# STM32F030.net
KiCad netlist of a schematic drawn in Altium Designer
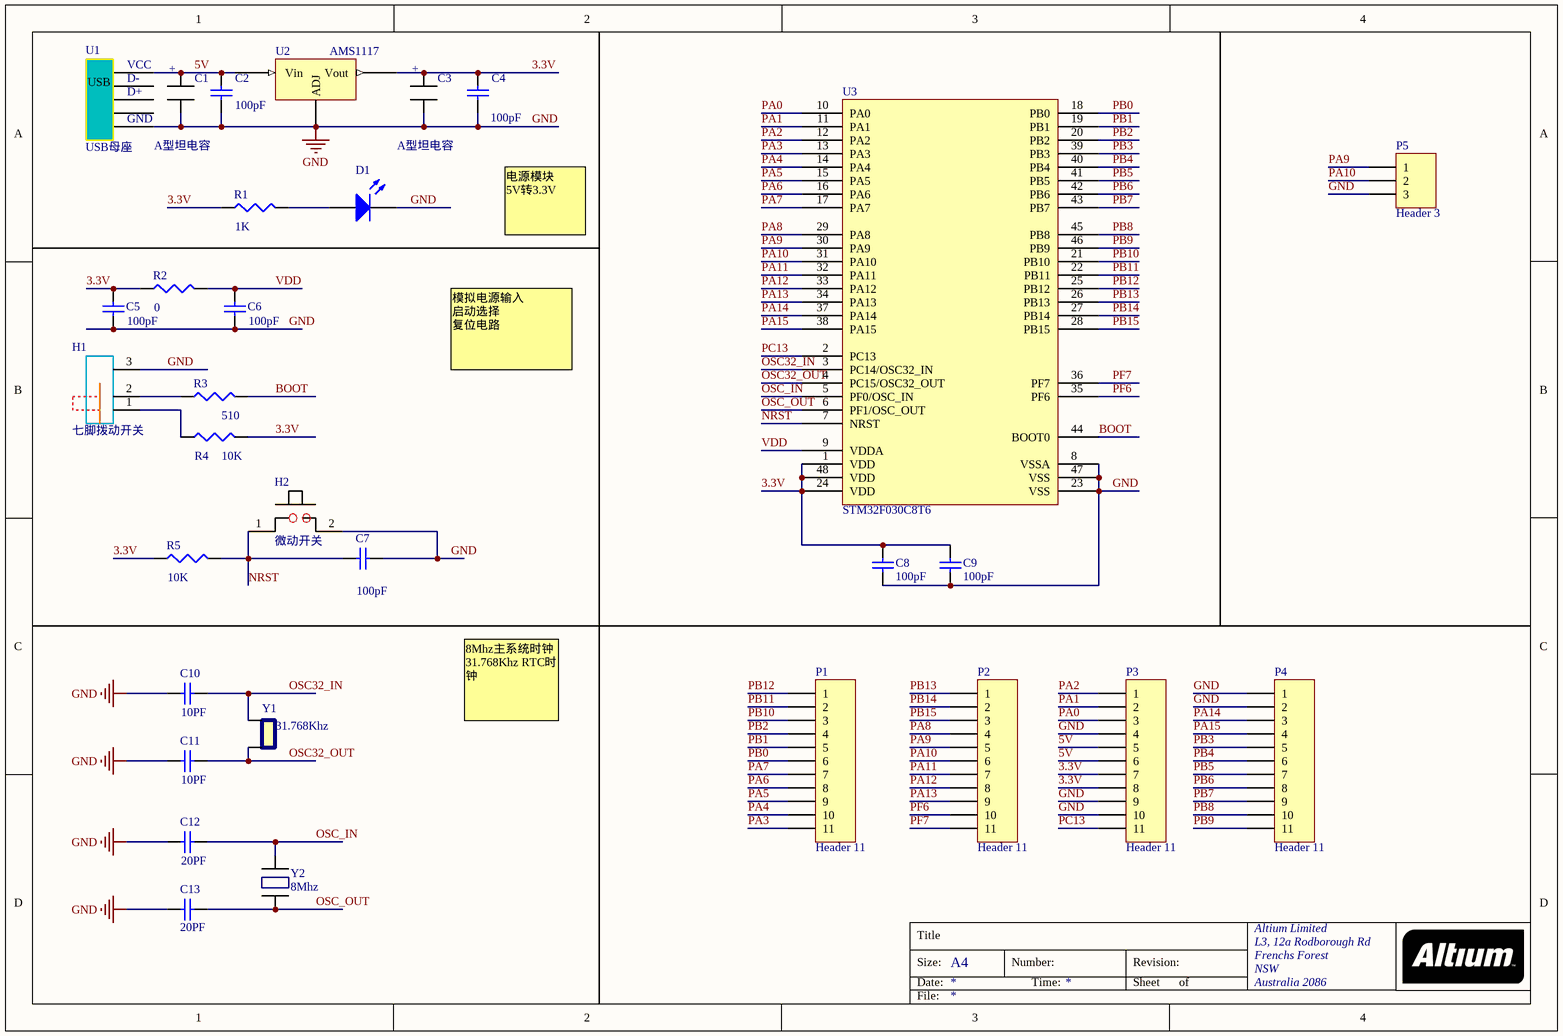
[diagram p0: STM32F030.SchDoc]

(export (version "E")
  (design (tool "Eeschema 10.0.6"))
  (components
    (comp (ref "C1")
      (value "A型坦电容")
      (footprint "A型坦电容")
      (description "C?")
      (libsource (lib "AD元件库") (part "A型坦电容"))
    )
    (comp (ref "C2")
      (value "100pF")
      (footprint "C1206")
      (description "Capacitor (Semiconductor SIM Model)")
      (fields (field (name "Comment") "0.1UF") (field (name "PUBLISHER") "Altium Limited"))
      (libsource (lib "Miscellaneous Devices") (part "Cap Semi"))
    )
    (comp (ref "C3")
      (value "A型坦电容")
      (footprint "A型坦电容")
      (description "C?")
      (libsource (lib "AD元件库") (part "A型坦电容"))
    )
    (comp (ref "C4")
      (value "100pF")
      (footprint "C1206")
      (description "Capacitor (Semiconductor SIM Model)")
      (fields (field (name "Comment") "0.1UF") (field (name "PUBLISHER") "Altium Limited"))
      (libsource (lib "Miscellaneous Devices") (part "Cap Semi"))
    )
    (comp (ref "C5")
      (value "100pF")
      (footprint "C1206")
      (description "Capacitor (Semiconductor SIM Model)")
      (fields (field (name "Comment") "0.1UF") (field (name "PUBLISHER") "Altium Limited"))
      (libsource (lib "Miscellaneous Devices") (part "Cap Semi"))
    )
    (comp (ref "C6")
      (value "100pF")
      (footprint "C1206")
      (description "Capacitor (Semiconductor SIM Model)")
      (fields (field (name "Comment") "0.1UF") (field (name "PUBLISHER") "Altium Limited"))
      (libsource (lib "Miscellaneous Devices") (part "Cap Semi"))
    )
    (comp (ref "C7")
      (value "100pF")
      (footprint "C1206")
      (description "Capacitor (Semiconductor SIM Model)")
      (fields (field (name "Comment") "0.1UF") (field (name "PUBLISHER") "Altium Limited"))
      (libsource (lib "Miscellaneous Devices") (part "Cap Semi"))
    )
    (comp (ref "C8")
      (value "100pF")
      (footprint "C1206")
      (description "Capacitor (Semiconductor SIM Model)")
      (fields (field (name "Comment") "0.1UF") (field (name "PUBLISHER") "Altium Limited"))
      (libsource (lib "Miscellaneous Devices") (part "Cap Semi"))
    )
    (comp (ref "C9")
      (value "100pF")
      (footprint "C1206")
      (description "Capacitor (Semiconductor SIM Model)")
      (fields (field (name "Comment") "0.1UF") (field (name "PUBLISHER") "Altium Limited"))
      (libsource (lib "Miscellaneous Devices") (part "Cap Semi"))
    )
    (comp (ref "C10")
      (value "10PF")
      (footprint "C1206")
      (description "Capacitor (Semiconductor SIM Model)")
      (fields (field (name "PUBLISHER") "Altium Limited"))
      (libsource (lib "Miscellaneous Devices") (part "Cap Semi"))
    )
    (comp (ref "C11")
      (value "10PF")
      (footprint "C1206")
      (description "Capacitor (Semiconductor SIM Model)")
      (fields (field (name "PUBLISHER") "Altium Limited"))
      (libsource (lib "Miscellaneous Devices") (part "Cap Semi"))
    )
    (comp (ref "C12")
      (value "20PF")
      (footprint "C1206")
      (description "Capacitor (Semiconductor SIM Model)")
      (fields (field (name "PUBLISHER") "Altium Limited"))
      (libsource (lib "Miscellaneous Devices") (part "Cap Semi"))
    )
    (comp (ref "C13")
      (value "20PF")
      (footprint "C1206")
      (description "Capacitor (Semiconductor SIM Model)")
      (fields (field (name "PUBLISHER") "Altium Limited"))
      (libsource (lib "Miscellaneous Devices") (part "Cap Semi"))
    )
    (comp (ref "D1")
      (value "LED")
      (footprint "3.2X1.6X1.1")
      (description "Typical RED, GREEN, YELLOW, AMBER GaAs LED")
      (fields (field (name "PUBLISHER") "Altium Limited"))
      (libsource (lib "Miscellaneous Devices") (part "LED2"))
    )
    (comp (ref "H1")
      (value "七脚拨动开关")
      (footprint "七脚拨动开磁")
      (description "H?")
      (libsource (lib "AD元件库") (part "七脚拨动开关"))
    )
    (comp (ref "H2")
      (value "微动开关")
      (footprint "微动开关")
      (description "H?")
      (libsource (lib "AD元件库") (part "微动开关"))
    )
    (comp (ref "P1")
      (value "Header 11")
      (footprint "HDR1X11")
      (description "Header, 11-Pin")
      (fields (field (name "PUBLISHER") "Altium Limited"))
      (libsource (lib "Miscellaneous Connectors") (part "Header 11"))
    )
    (comp (ref "P2")
      (value "Header 11")
      (footprint "HDR1X11")
      (description "Header, 11-Pin")
      (fields (field (name "PUBLISHER") "Altium Limited"))
      (libsource (lib "Miscellaneous Connectors") (part "Header 11"))
    )
    (comp (ref "P3")
      (value "Header 11")
      (footprint "HDR1X11")
      (description "Header, 11-Pin")
      (fields (field (name "PUBLISHER") "Altium Limited"))
      (libsource (lib "Miscellaneous Connectors") (part "Header 11"))
    )
    (comp (ref "P4")
      (value "Header 11")
      (footprint "HDR1X11")
      (description "Header, 11-Pin")
      (fields (field (name "PUBLISHER") "Altium Limited"))
      (libsource (lib "Miscellaneous Connectors") (part "Header 11"))
    )
    (comp (ref "P5")
      (value "Header 3")
      (footprint "HDR1X3")
      (description "Header, 3-Pin")
      (fields (field (name "PUBLISHER") "Altium Limited"))
      (libsource (lib "Miscellaneous Connectors") (part "Header 3"))
    )
    (comp (ref "R1")
      (value "1K")
      (footprint "14-1210")
      (description "Resistor")
      (fields (field (name "PUBLISHER") "Altium Limited"))
      (libsource (lib "Miscellaneous Devices") (part "Res3"))
    )
    (comp (ref "R2")
      (value "0")
      (footprint "14-1210")
      (description "Resistor")
      (fields (field (name "PUBLISHER") "Altium Limited"))
      (libsource (lib "Miscellaneous Devices") (part "Res3"))
    )
    (comp (ref "R3")
      (value "510")
      (footprint "14-1210")
      (description "Resistor")
      (fields (field (name "PUBLISHER") "Altium Limited"))
      (libsource (lib "Miscellaneous Devices") (part "Res3"))
    )
    (comp (ref "R4")
      (value "10K")
      (footprint "14-1210")
      (description "Resistor")
      (fields (field (name "PUBLISHER") "Altium Limited"))
      (libsource (lib "Miscellaneous Devices") (part "Res3"))
    )
    (comp (ref "R5")
      (value "10K")
      (footprint "14-1210")
      (description "Resistor")
      (fields (field (name "PUBLISHER") "Altium Limited"))
      (libsource (lib "Miscellaneous Devices") (part "Res3"))
    )
    (comp (ref "U1")
      (value "USB母座")
      (footprint "MicroUSB母座")
      (description "U?")
      (libsource (lib "AD元件库") (part "MicroUSB母座"))
    )
    (comp (ref "U2")
      (value "AMS1117")
      (footprint "AMS1117")
      (description "U?")
      (libsource (lib "AD元件库") (part "AMS1117"))
    )
    (comp (ref "U3")
      (value "STM32F030C8T6")
      (footprint "STM32F030C8T6")
      (description "U?")
      (libsource (lib "AD元件库") (part "STM32F030C8T6"))
    )
    (comp (ref "Y1")
      (value "31.768Khz")
      (footprint "31.768khz(3*8)")
      (description "Y?")
      (libsource (lib "AD元件库") (part "31.768khz(3*8)"))
    )
    (comp (ref "Y2") (value "8Mhz") (footprint "晶振") (description "Y?") (libsource (lib "AD元件库") (part "晶振")))
  )
  (nets
    (net (code "1") (name "/3.3V") (class "Default")
      (node (ref "C3") (pin "2") (pinfunction "+_2") (pintype "passive"))
      (node (ref "C4") (pin "2") (pinfunction "2_2") (pintype "passive"))
      (node (ref "C5") (pin "2") (pinfunction "2_2") (pintype "passive"))
      (node (ref "C8") (pin "2") (pinfunction "2_2") (pintype "passive"))
      (node (ref "C9") (pin "2") (pinfunction "2_2") (pintype "passive"))
      (node (ref "P3") (pin "7") (pinfunction "7_7") (pintype "passive"))
      (node (ref "P3") (pin "8") (pinfunction "8_8") (pintype "passive"))
      (node (ref "R1") (pin "1") (pinfunction "1_1") (pintype "passive"))
      (node (ref "R2") (pin "1") (pinfunction "1_1") (pintype "passive"))
      (node (ref "R4") (pin "2") (pinfunction "2_2") (pintype "passive"))
      (node (ref "R5") (pin "1") (pinfunction "1_1") (pintype "passive"))
      (node (ref "U2") (pin "2") (pinfunction "Vout_2") (pintype "output"))
      (node (ref "U3") (pin "1") (pinfunction "VDD_1") (pintype "passive"))
      (node (ref "U3") (pin "24") (pinfunction "VDD_24") (pintype "passive"))
      (node (ref "U3") (pin "48") (pinfunction "VDD_48") (pintype "passive"))
    )
    (net (code "2") (name "/5V") (class "Default")
      (node (ref "C1") (pin "2") (pinfunction "+_2") (pintype "passive"))
      (node (ref "C2") (pin "2") (pinfunction "2_2") (pintype "passive"))
      (node (ref "P3") (pin "5") (pinfunction "5_5") (pintype "passive"))
      (node (ref "P3") (pin "6") (pinfunction "6_6") (pintype "passive"))
      (node (ref "U1") (pin "1") (pintype "passive"))
      (node (ref "U2") (pin "3") (pinfunction "Vin_3") (pintype "input"))
    )
    (net (code "3") (name "/BOOT") (class "Default")
      (node (ref "R3") (pin "2") (pinfunction "2_2") (pintype "passive"))
      (node (ref "U3") (pin "44") (pinfunction "BOOT0_44") (pintype "passive"))
    )
    (net (code "4") (name "/NRST") (class "Default")
      (node (ref "C7") (pin "1") (pinfunction "1_1") (pintype "passive"))
      (node (ref "H2") (pin "1") (pinfunction "104_1") (pintype "passive"))
      (node (ref "R5") (pin "2") (pinfunction "2_2") (pintype "passive"))
      (node (ref "U3") (pin "7") (pinfunction "NRST_7") (pintype "passive"))
    )
    (net (code "5") (name "/OSC32_IN") (class "Default")
      (node (ref "C10") (pin "2") (pinfunction "2_2") (pintype "passive"))
      (node (ref "U3") (pin "3") (pinfunction "PC14/OSC32_IN_3") (pintype "passive"))
      (node (ref "Y1") (pin "0") (pinfunction "0_0") (pintype "passive"))
    )
    (net (code "6") (name "/OSC32_OUT") (class "Default")
      (node (ref "C11") (pin "2") (pinfunction "2_2") (pintype "passive"))
      (node (ref "U3") (pin "4") (pinfunction "PC15/OSC32_OUT_4") (pintype "passive"))
      (node (ref "Y1") (pin "1") (pinfunction "1_1") (pintype "passive"))
    )
    (net (code "7") (name "/OSC_IN") (class "Default")
      (node (ref "C12") (pin "2") (pinfunction "2_2") (pintype "passive"))
      (node (ref "U3") (pin "5") (pinfunction "PF0/OSC_IN_5") (pintype "passive"))
      (node (ref "Y2") (pin "2") (pintype "passive"))
    )
    (net (code "8") (name "/OSC_OUT") (class "Default")
      (node (ref "C13") (pin "2") (pinfunction "2_2") (pintype "passive"))
      (node (ref "U3") (pin "6") (pinfunction "PF1/OSC_OUT_6") (pintype "passive"))
      (node (ref "Y2") (pin "1") (pintype "passive"))
    )
    (net (code "9") (name "/PA0") (class "Default")
      (node (ref "P3") (pin "3") (pinfunction "3_3") (pintype "passive"))
      (node (ref "U3") (pin "10") (pinfunction "PA0_10") (pintype "passive"))
    )
    (net (code "10") (name "/PA1") (class "Default")
      (node (ref "P3") (pin "2") (pinfunction "2_2") (pintype "passive"))
      (node (ref "U3") (pin "11") (pinfunction "PA1_11") (pintype "passive"))
    )
    (net (code "11") (name "/PA2") (class "Default")
      (node (ref "P3") (pin "1") (pinfunction "1_1") (pintype "passive"))
      (node (ref "U3") (pin "12") (pinfunction "PA2_12") (pintype "passive"))
    )
    (net (code "12") (name "/PA3") (class "Default")
      (node (ref "P1") (pin "11") (pinfunction "11_11") (pintype "passive"))
      (node (ref "U3") (pin "13") (pinfunction "PA3_13") (pintype "passive"))
    )
    (net (code "13") (name "/PA4") (class "Default")
      (node (ref "P1") (pin "10") (pinfunction "10_10") (pintype "passive"))
      (node (ref "U3") (pin "14") (pinfunction "PA4_14") (pintype "passive"))
    )
    (net (code "14") (name "/PA5") (class "Default")
      (node (ref "P1") (pin "9") (pinfunction "9_9") (pintype "passive"))
      (node (ref "U3") (pin "15") (pinfunction "PA5_15") (pintype "passive"))
    )
    (net (code "15") (name "/PA6") (class "Default")
      (node (ref "P1") (pin "8") (pinfunction "8_8") (pintype "passive"))
      (node (ref "U3") (pin "16") (pinfunction "PA6_16") (pintype "passive"))
    )
    (net (code "16") (name "/PA7") (class "Default")
      (node (ref "P1") (pin "7") (pinfunction "7_7") (pintype "passive"))
      (node (ref "U3") (pin "17") (pinfunction "PA7_17") (pintype "passive"))
    )
    (net (code "17") (name "/PA8") (class "Default")
      (node (ref "P2") (pin "4") (pinfunction "4_4") (pintype "passive"))
      (node (ref "U3") (pin "29") (pinfunction "PA8_29") (pintype "passive"))
    )
    (net (code "18") (name "/PA9") (class "Default")
      (node (ref "P2") (pin "5") (pinfunction "5_5") (pintype "passive"))
      (node (ref "P5") (pin "1") (pinfunction "1_1") (pintype "passive"))
      (node (ref "U3") (pin "30") (pinfunction "PA9_30") (pintype "passive"))
    )
    (net (code "19") (name "/PA10") (class "Default")
      (node (ref "P2") (pin "6") (pinfunction "6_6") (pintype "passive"))
      (node (ref "P5") (pin "2") (pinfunction "2_2") (pintype "passive"))
      (node (ref "U3") (pin "31") (pinfunction "PA10_31") (pintype "passive"))
    )
    (net (code "20") (name "/PA11") (class "Default")
      (node (ref "P2") (pin "7") (pinfunction "7_7") (pintype "passive"))
      (node (ref "U3") (pin "32") (pinfunction "PA11_32") (pintype "passive"))
    )
    (net (code "21") (name "/PA12") (class "Default")
      (node (ref "P2") (pin "8") (pinfunction "8_8") (pintype "passive"))
      (node (ref "U3") (pin "33") (pinfunction "PA12_33") (pintype "passive"))
    )
    (net (code "22") (name "/PA13") (class "Default")
      (node (ref "P2") (pin "9") (pinfunction "9_9") (pintype "passive"))
      (node (ref "U3") (pin "34") (pinfunction "PA13_34") (pintype "passive"))
    )
    (net (code "23") (name "/PA14") (class "Default")
      (node (ref "P4") (pin "3") (pinfunction "3_3") (pintype "passive"))
      (node (ref "U3") (pin "37") (pinfunction "PA14_37") (pintype "passive"))
    )
    (net (code "24") (name "/PA15") (class "Default")
      (node (ref "P4") (pin "4") (pinfunction "4_4") (pintype "passive"))
      (node (ref "U3") (pin "38") (pinfunction "PA15_38") (pintype "passive"))
    )
    (net (code "25") (name "/PB0") (class "Default")
      (node (ref "P1") (pin "6") (pinfunction "6_6") (pintype "passive"))
      (node (ref "U3") (pin "18") (pinfunction "PB0_18") (pintype "passive"))
    )
    (net (code "26") (name "/PB1") (class "Default")
      (node (ref "P1") (pin "5") (pinfunction "5_5") (pintype "passive"))
      (node (ref "U3") (pin "19") (pinfunction "PB1_19") (pintype "passive"))
    )
    (net (code "27") (name "/PB2") (class "Default")
      (node (ref "P1") (pin "4") (pinfunction "4_4") (pintype "passive"))
      (node (ref "U3") (pin "20") (pinfunction "PB2_20") (pintype "passive"))
    )
    (net (code "28") (name "/PB3") (class "Default")
      (node (ref "P4") (pin "5") (pinfunction "5_5") (pintype "passive"))
      (node (ref "U3") (pin "39") (pinfunction "PB3_39") (pintype "passive"))
    )
    (net (code "29") (name "/PB4") (class "Default")
      (node (ref "P4") (pin "6") (pinfunction "6_6") (pintype "passive"))
      (node (ref "U3") (pin "40") (pinfunction "PB4_40") (pintype "passive"))
    )
    (net (code "30") (name "/PB5") (class "Default")
      (node (ref "P4") (pin "7") (pinfunction "7_7") (pintype "passive"))
      (node (ref "U3") (pin "41") (pinfunction "PB5_41") (pintype "passive"))
    )
    (net (code "31") (name "/PB6") (class "Default")
      (node (ref "P4") (pin "8") (pinfunction "8_8") (pintype "passive"))
      (node (ref "U3") (pin "42") (pinfunction "PB6_42") (pintype "passive"))
    )
    (net (code "32") (name "/PB7") (class "Default")
      (node (ref "P4") (pin "9") (pinfunction "9_9") (pintype "passive"))
      (node (ref "U3") (pin "43") (pinfunction "PB7_43") (pintype "passive"))
    )
    (net (code "33") (name "/PB8") (class "Default")
      (node (ref "P4") (pin "10") (pinfunction "10_10") (pintype "passive"))
      (node (ref "U3") (pin "45") (pinfunction "PB8_45") (pintype "passive"))
    )
    (net (code "34") (name "/PB9") (class "Default")
      (node (ref "P4") (pin "11") (pinfunction "11_11") (pintype "passive"))
      (node (ref "U3") (pin "46") (pinfunction "PB9_46") (pintype "passive"))
    )
    (net (code "35") (name "/PB10") (class "Default")
      (node (ref "P1") (pin "3") (pinfunction "3_3") (pintype "passive"))
      (node (ref "U3") (pin "21") (pinfunction "PB10_21") (pintype "passive"))
    )
    (net (code "36") (name "/PB11") (class "Default")
      (node (ref "P1") (pin "2") (pinfunction "2_2") (pintype "passive"))
      (node (ref "U3") (pin "22") (pinfunction "PB11_22") (pintype "passive"))
    )
    (net (code "37") (name "/PB12") (class "Default")
      (node (ref "P1") (pin "1") (pinfunction "1_1") (pintype "passive"))
      (node (ref "U3") (pin "25") (pinfunction "PB12_25") (pintype "passive"))
    )
    (net (code "38") (name "/PB13") (class "Default")
      (node (ref "P2") (pin "1") (pinfunction "1_1") (pintype "passive"))
      (node (ref "U3") (pin "26") (pinfunction "PB13_26") (pintype "passive"))
    )
    (net (code "39") (name "/PB14") (class "Default")
      (node (ref "P2") (pin "2") (pinfunction "2_2") (pintype "passive"))
      (node (ref "U3") (pin "27") (pinfunction "PB14_27") (pintype "passive"))
    )
    (net (code "40") (name "/PB15") (class "Default")
      (node (ref "P2") (pin "3") (pinfunction "3_3") (pintype "passive"))
      (node (ref "U3") (pin "28") (pinfunction "PB15_28") (pintype "passive"))
    )
    (net (code "41") (name "/PC13") (class "Default")
      (node (ref "P3") (pin "11") (pinfunction "11_11") (pintype "passive"))
      (node (ref "U3") (pin "2") (pinfunction "PC13_2") (pintype "passive"))
    )
    (net (code "42") (name "/PF6") (class "Default")
      (node (ref "P2") (pin "10") (pinfunction "10_10") (pintype "passive"))
      (node (ref "U3") (pin "35") (pinfunction "PF6_35") (pintype "passive"))
    )
    (net (code "43") (name "/PF7") (class "Default")
      (node (ref "P2") (pin "11") (pinfunction "11_11") (pintype "passive"))
      (node (ref "U3") (pin "36") (pinfunction "PF7_36") (pintype "passive"))
    )
    (net (code "44") (name "/VDD") (class "Default")
      (node (ref "C6") (pin "2") (pinfunction "2_2") (pintype "passive"))
      (node (ref "R2") (pin "2") (pinfunction "2_2") (pintype "passive"))
      (node (ref "U3") (pin "9") (pinfunction "VDDA_9") (pintype "passive"))
    )
    (net (code "45") (name "GND") (class "Default")
      (node (ref "C1") (pin "1") (pintype "passive"))
      (node (ref "C10") (pin "1") (pinfunction "1_1") (pintype "passive"))
      (node (ref "C11") (pin "1") (pinfunction "1_1") (pintype "passive"))
      (node (ref "C12") (pin "1") (pinfunction "1_1") (pintype "passive"))
      (node (ref "C13") (pin "1") (pinfunction "1_1") (pintype "passive"))
      (node (ref "C2") (pin "1") (pinfunction "1_1") (pintype "passive"))
      (node (ref "C3") (pin "1") (pintype "passive"))
      (node (ref "C4") (pin "1") (pinfunction "1_1") (pintype "passive"))
      (node (ref "C5") (pin "1") (pinfunction "1_1") (pintype "passive"))
      (node (ref "C6") (pin "1") (pinfunction "1_1") (pintype "passive"))
      (node (ref "C7") (pin "2") (pinfunction "2_2") (pintype "passive"))
      (node (ref "C8") (pin "1") (pinfunction "1_1") (pintype "passive"))
      (node (ref "C9") (pin "1") (pinfunction "1_1") (pintype "passive"))
      (node (ref "D1") (pin "2") (pinfunction "K_2") (pintype "passive"))
      (node (ref "H1") (pin "3") (pinfunction "5_3") (pintype "passive"))
      (node (ref "H2") (pin "2") (pinfunction "105_2") (pintype "passive"))
      (node (ref "P3") (pin "10") (pinfunction "10_10") (pintype "passive"))
      (node (ref "P3") (pin "4") (pinfunction "4_4") (pintype "passive"))
      (node (ref "P3") (pin "9") (pinfunction "9_9") (pintype "passive"))
      (node (ref "P4") (pin "1") (pinfunction "1_1") (pintype "passive"))
      (node (ref "P4") (pin "2") (pinfunction "2_2") (pintype "passive"))
      (node (ref "P5") (pin "3") (pinfunction "3_3") (pintype "passive"))
      (node (ref "U1") (pin "5") (pintype "passive"))
      (node (ref "U2") (pin "1") (pinfunction "ADJ_1") (pintype "passive"))
      (node (ref "U3") (pin "23") (pinfunction "VSS_23") (pintype "passive"))
      (node (ref "U3") (pin "47") (pinfunction "VSS_47") (pintype "passive"))
      (node (ref "U3") (pin "8") (pinfunction "VSSA_8") (pintype "passive"))
    )
    (net (code "46") (name "Net-(D1-A)") (class "Default")
      (node (ref "D1") (pin "1") (pinfunction "A_1") (pintype "passive"))
      (node (ref "R1") (pin "2") (pinfunction "2_2") (pintype "passive"))
    )
    (net (code "47") (name "Net-(H1-3)") (class "Default")
      (node (ref "H1") (pin "1") (pinfunction "3_1") (pintype "passive"))
      (node (ref "R4") (pin "1") (pinfunction "1_1") (pintype "passive"))
    )
    (net (code "48") (name "Net-(H1-4)") (class "Default")
      (node (ref "H1") (pin "2") (pinfunction "4_2") (pintype "passive"))
      (node (ref "R3") (pin "1") (pinfunction "1_1") (pintype "passive"))
    )
    (net (code "49") (name "unconnected-(U1-Pad2)") (class "Default")
      (node (ref "U1") (pin "2") (pintype "passive"))
    )
    (net (code "50") (name "unconnected-(U1-Pad3)") (class "Default")
      (node (ref "U1") (pin "3") (pintype "passive"))
    )
    (net (code "51") (name "unconnected-(U1-Pad4)") (class "Default")
      (node (ref "U1") (pin "4") (pintype "passive"))
    )
  )
)
